# Starter_Shield.net
KiCad netlist of a schematic drawn in EAGLE
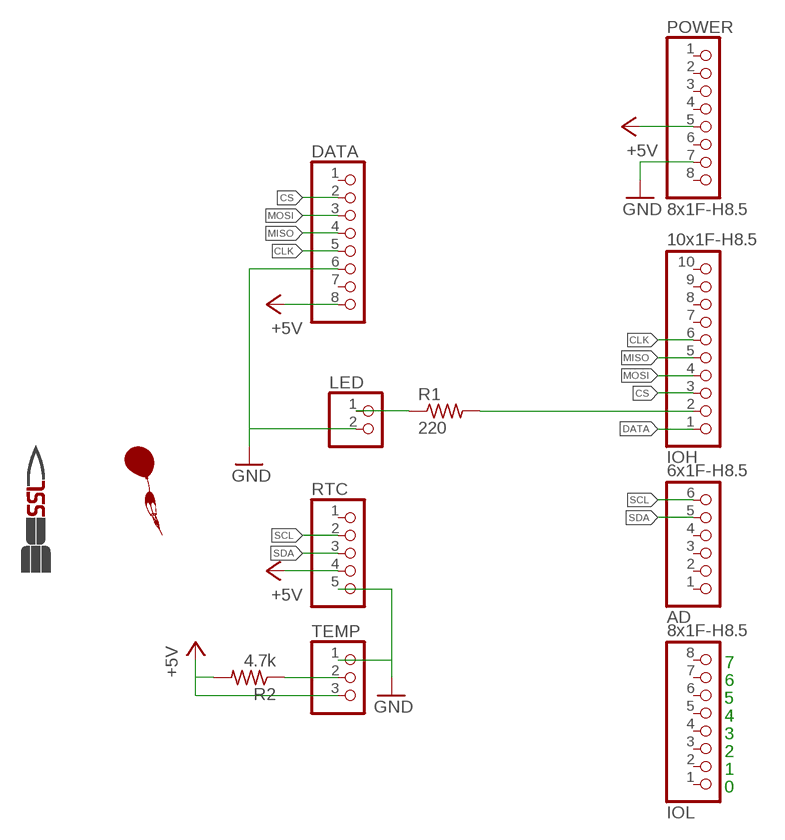
[diagram p0: schematic, sheet 1]

(export (version "E")
  (design (tool "Eeschema 10.0.6"))
  (components
    (comp (ref "AD")
      (value "6x1F-H8.5")
      (footprint "eagle-import:1X06")
      (libsource (lib "eagle-import") (part "PINHD-1X6"))
    )
    (comp (ref "DATA")
      (value "PINHD-1X8")
      (footprint "eagle-import:1X08")
      (libsource (lib "eagle-import") (part "pinhead_PINHD-1X8"))
    )
    (comp (ref "IMAG1")
      (value "SSL.53IN")
      (footprint "eagle-import:SSL_.53IN")
      (libsource (lib "eagle-import") (part "SSL.53IN"))
    )
    (comp (ref "IOH")
      (value "10x1F-H8.5")
      (footprint "eagle-import:1X10")
      (libsource (lib "eagle-import") (part "PINHD-1X10_ARD"))
    )
    (comp (ref "IOL")
      (value "8x1F-H8.5")
      (footprint "eagle-import:1X08")
      (libsource (lib "eagle-import") (part "PINHD-1X8"))
    )
    (comp (ref "LED")
      (value "PINHD-1X2")
      (footprint "eagle-import:1X02")
      (libsource (lib "eagle-import") (part "PINHD-1X2"))
    )
    (comp (ref "POWER")
      (value "8x1F-H8.5")
      (footprint "eagle-import:1X08")
      (libsource (lib "eagle-import") (part "PINHD-1X8"))
    )
    (comp (ref "R1")
      (value "220")
      (footprint "eagle-import:0207_10")
      (libsource (lib "eagle-import") (part "R-US_0207/10"))
    )
    (comp (ref "R2")
      (value "4.7k")
      (footprint "eagle-import:0207_10")
      (libsource (lib "eagle-import") (part "R-US_0207/10"))
    )
    (comp (ref "RTC")
      (value "PINHD-1X5")
      (footprint "eagle-import:1X05")
      (libsource (lib "eagle-import") (part "PINHD-1X5"))
    )
    (comp (ref "TEMP")
      (value "PINHD-1X3")
      (footprint "eagle-import:1X03")
      (libsource (lib "eagle-import") (part "PINHD-1X3"))
    )
    (comp (ref "U$1")
      (value "BALLOON")
      (footprint "eagle-import:BALLOON")
      (libsource (lib "eagle-import") (part "BALLOON"))
    )
  )
  (nets
    (net (code "1") (name "+5V") (class "Default")
      (node (ref "DATA") (pin "8") (pinfunction "8_8") (pintype "passive"))
      (node (ref "POWER") (pin "5") (pinfunction "5_5") (pintype "passive"))
      (node (ref "R2") (pin "2") (pinfunction "2_2") (pintype "passive"))
      (node (ref "RTC") (pin "4") (pinfunction "4_4") (pintype "passive"))
      (node (ref "TEMP") (pin "3") (pinfunction "3_3") (pintype "passive"))
    )
    (net (code "2") (name "CLK") (class "Default")
      (node (ref "DATA") (pin "5") (pinfunction "5_5") (pintype "passive"))
      (node (ref "IOH") (pin "6") (pinfunction "6_6") (pintype "passive"))
    )
    (net (code "3") (name "CS") (class "Default")
      (node (ref "DATA") (pin "2") (pinfunction "2_2") (pintype "passive"))
      (node (ref "IOH") (pin "3") (pinfunction "3_3") (pintype "passive"))
    )
    (net (code "4") (name "DATA") (class "Default")
      (node (ref "IOH") (pin "1") (pinfunction "1_1") (pintype "passive"))
      (node (ref "R2") (pin "1") (pinfunction "1_1") (pintype "passive"))
      (node (ref "TEMP") (pin "2") (pinfunction "2_2") (pintype "passive"))
    )
    (net (code "5") (name "GND") (class "Default")
      (node (ref "DATA") (pin "6") (pinfunction "6_6") (pintype "passive"))
      (node (ref "LED") (pin "2") (pinfunction "2_2") (pintype "passive"))
      (node (ref "POWER") (pin "7") (pinfunction "7_7") (pintype "passive"))
      (node (ref "RTC") (pin "5") (pinfunction "5_5") (pintype "passive"))
      (node (ref "TEMP") (pin "1") (pinfunction "1_1") (pintype "passive"))
    )
    (net (code "6") (name "MISO") (class "Default")
      (node (ref "DATA") (pin "4") (pinfunction "4_4") (pintype "passive"))
      (node (ref "IOH") (pin "5") (pinfunction "5_5") (pintype "passive"))
    )
    (net (code "7") (name "MOSI") (class "Default")
      (node (ref "DATA") (pin "3") (pinfunction "3_3") (pintype "passive"))
      (node (ref "IOH") (pin "4") (pinfunction "4_4") (pintype "passive"))
    )
    (net (code "8") (name "Net-(IOH-Pad2)") (class "Default")
      (node (ref "IOH") (pin "2") (pinfunction "2_2") (pintype "passive"))
      (node (ref "R1") (pin "2") (pinfunction "2_2") (pintype "passive"))
    )
    (net (code "9") (name "Net-(LED-Pad1)") (class "Default")
      (node (ref "LED") (pin "1") (pinfunction "1_1") (pintype "passive"))
      (node (ref "R1") (pin "1") (pinfunction "1_1") (pintype "passive"))
    )
    (net (code "10") (name "SCL") (class "Default")
      (node (ref "AD") (pin "6") (pinfunction "6_6") (pintype "passive"))
      (node (ref "RTC") (pin "2") (pinfunction "2_2") (pintype "passive"))
    )
    (net (code "11") (name "SDA") (class "Default")
      (node (ref "AD") (pin "5") (pinfunction "5_5") (pintype "passive"))
      (node (ref "RTC") (pin "3") (pinfunction "3_3") (pintype "passive"))
    )
    (net (code "12") (name "unconnected-(AD-Pad1)") (class "Default")
      (node (ref "AD") (pin "1") (pinfunction "1_1") (pintype "passive"))
    )
    (net (code "13") (name "unconnected-(AD-Pad2)") (class "Default")
      (node (ref "AD") (pin "2") (pinfunction "2_2") (pintype "passive"))
    )
    (net (code "14") (name "unconnected-(AD-Pad3)") (class "Default")
      (node (ref "AD") (pin "3") (pinfunction "3_3") (pintype "passive"))
    )
    (net (code "15") (name "unconnected-(AD-Pad4)") (class "Default")
      (node (ref "AD") (pin "4") (pinfunction "4_4") (pintype "passive"))
    )
    (net (code "16") (name "unconnected-(DATA-Pad1)") (class "Default")
      (node (ref "DATA") (pin "1") (pinfunction "1_1") (pintype "passive"))
    )
    (net (code "17") (name "unconnected-(DATA-Pad7)") (class "Default")
      (node (ref "DATA") (pin "7") (pinfunction "7_7") (pintype "passive"))
    )
    (net (code "18") (name "unconnected-(IOH-Pad7)") (class "Default")
      (node (ref "IOH") (pin "7") (pinfunction "7_7") (pintype "passive"))
    )
    (net (code "19") (name "unconnected-(IOH-Pad8)") (class "Default")
      (node (ref "IOH") (pin "8") (pinfunction "8_8") (pintype "passive"))
    )
    (net (code "20") (name "unconnected-(IOH-Pad9)") (class "Default")
      (node (ref "IOH") (pin "9") (pinfunction "9_9") (pintype "passive"))
    )
    (net (code "21") (name "unconnected-(IOH-Pad10)") (class "Default")
      (node (ref "IOH") (pin "10") (pinfunction "10_10") (pintype "passive"))
    )
    (net (code "22") (name "unconnected-(IOL-Pad1)") (class "Default")
      (node (ref "IOL") (pin "1") (pinfunction "1_1") (pintype "passive"))
    )
    (net (code "23") (name "unconnected-(IOL-Pad2)") (class "Default")
      (node (ref "IOL") (pin "2") (pinfunction "2_2") (pintype "passive"))
    )
    (net (code "24") (name "unconnected-(IOL-Pad3)") (class "Default")
      (node (ref "IOL") (pin "3") (pinfunction "3_3") (pintype "passive"))
    )
    (net (code "25") (name "unconnected-(IOL-Pad4)") (class "Default")
      (node (ref "IOL") (pin "4") (pinfunction "4_4") (pintype "passive"))
    )
    (net (code "26") (name "unconnected-(IOL-Pad5)") (class "Default")
      (node (ref "IOL") (pin "5") (pinfunction "5_5") (pintype "passive"))
    )
    (net (code "27") (name "unconnected-(IOL-Pad6)") (class "Default")
      (node (ref "IOL") (pin "6") (pinfunction "6_6") (pintype "passive"))
    )
    (net (code "28") (name "unconnected-(IOL-Pad7)") (class "Default")
      (node (ref "IOL") (pin "7") (pinfunction "7_7") (pintype "passive"))
    )
    (net (code "29") (name "unconnected-(IOL-Pad8)") (class "Default")
      (node (ref "IOL") (pin "8") (pinfunction "8_8") (pintype "passive"))
    )
    (net (code "30") (name "unconnected-(POWER-Pad1)") (class "Default")
      (node (ref "POWER") (pin "1") (pinfunction "1_1") (pintype "passive"))
    )
    (net (code "31") (name "unconnected-(POWER-Pad2)") (class "Default")
      (node (ref "POWER") (pin "2") (pinfunction "2_2") (pintype "passive"))
    )
    (net (code "32") (name "unconnected-(POWER-Pad3)") (class "Default")
      (node (ref "POWER") (pin "3") (pinfunction "3_3") (pintype "passive"))
    )
    (net (code "33") (name "unconnected-(POWER-Pad4)") (class "Default")
      (node (ref "POWER") (pin "4") (pinfunction "4_4") (pintype "passive"))
    )
    (net (code "34") (name "unconnected-(POWER-Pad6)") (class "Default")
      (node (ref "POWER") (pin "6") (pinfunction "6_6") (pintype "passive"))
    )
    (net (code "35") (name "unconnected-(POWER-Pad8)") (class "Default")
      (node (ref "POWER") (pin "8") (pinfunction "8_8") (pintype "passive"))
    )
    (net (code "36") (name "unconnected-(RTC-Pad1)") (class "Default")
      (node (ref "RTC") (pin "1") (pinfunction "1_1") (pintype "passive"))
    )
  )
)
